# STM32F103C8BRD.net
KiCad netlist of a schematic drawn in EAGLE
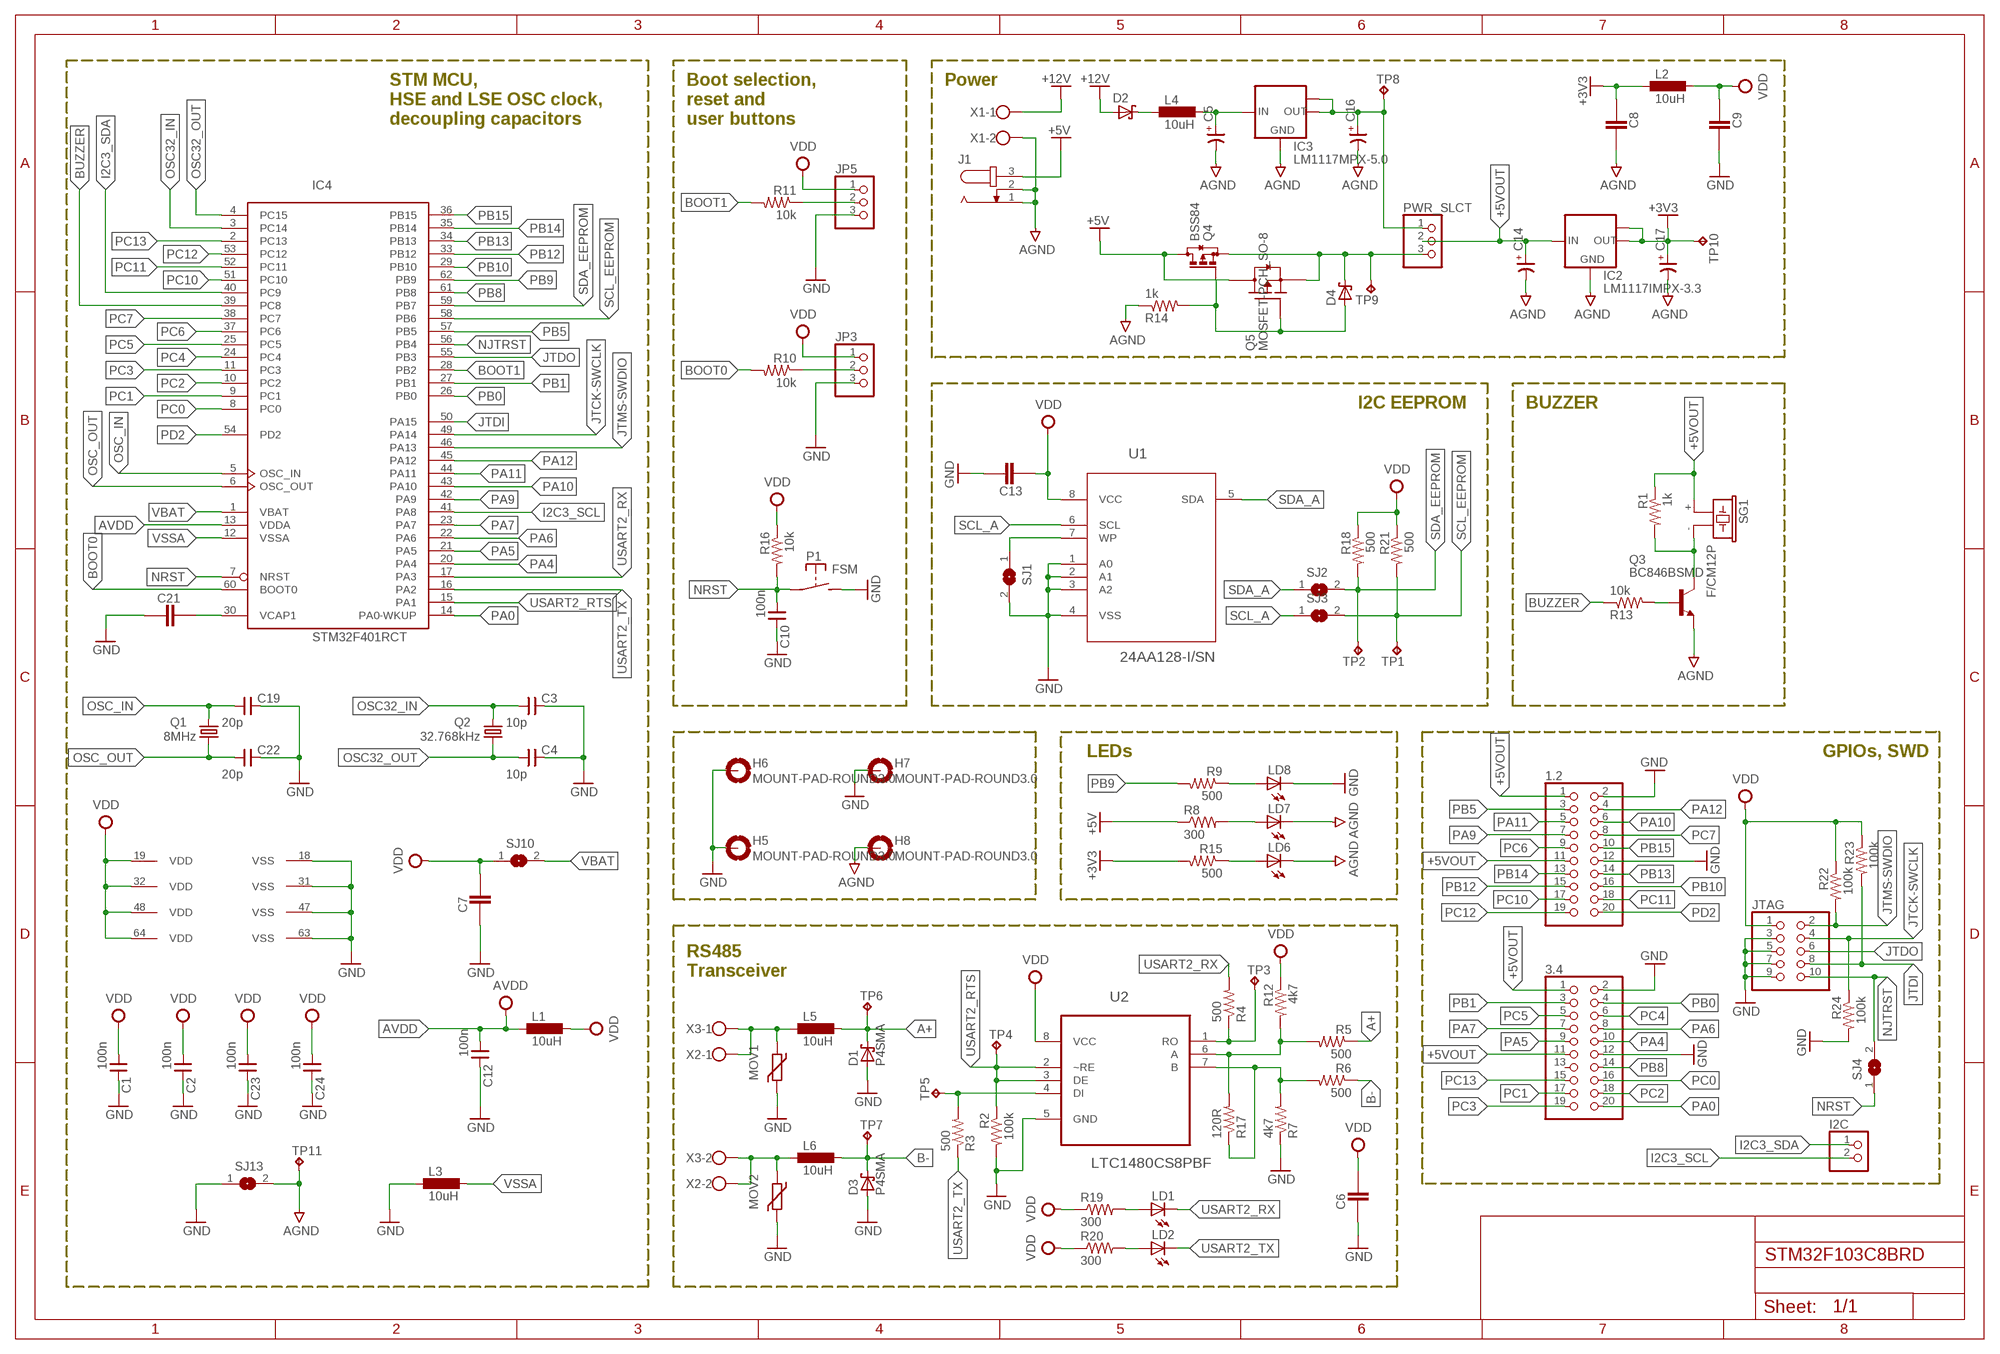
[diagram p0: schematic, sheet 1]

(export (version "E")
  (design (tool "Eeschema 10.0.6"))
  (components
    (comp (ref "1.2")
      (value "PINHD-2X10")
      (footprint "eagle-import:2X10")
      (libsource (lib "eagle-import") (part "PINHD-2X10"))
    )
    (comp (ref "3.4")
      (value "PINHD-2X10")
      (footprint "eagle-import:2X10")
      (libsource (lib "eagle-import") (part "PINHD-2X10"))
    )
    (comp (ref "C1")
      (value "100n")
      (footprint "eagle-import:0805")
      (libsource (lib "eagle-import") (part "CNP-0805"))
    )
    (comp (ref "C2")
      (value "100n")
      (footprint "eagle-import:0805")
      (libsource (lib "eagle-import") (part "CNP-0805"))
    )
    (comp (ref "C3")
      (value "10p")
      (footprint "eagle-import:0805")
      (libsource (lib "eagle-import") (part "CNP-0805"))
    )
    (comp (ref "C4")
      (value "10p")
      (footprint "eagle-import:0805")
      (libsource (lib "eagle-import") (part "CNP-0805"))
    )
    (comp (ref "C5")
      (value "CP-3258-TE-B")
      (footprint "eagle-import:3528-TE-B")
      (libsource (lib "eagle-import") (part "CP-3258-TE-B"))
    )
    (comp (ref "C6")
      (value "CAPACITOR_1206")
      (footprint "eagle-import:CAPC3215X168N")
      (libsource (lib "eagle-import") (part "CAPACITOR_1206"))
    )
    (comp (ref "C7")
      (value "CAPACITOR_1206")
      (footprint "eagle-import:CAPC3215X168N")
      (libsource (lib "eagle-import") (part "CAPACITOR_1206"))
    )
    (comp (ref "C8")
      (value "CAPACITOR_1206")
      (footprint "eagle-import:CAPC3215X168N")
      (libsource (lib "eagle-import") (part "CAPACITOR_1206"))
    )
    (comp (ref "C9")
      (value "CAPACITOR_1206")
      (footprint "eagle-import:CAPC3215X168N")
      (libsource (lib "eagle-import") (part "CAPACITOR_1206"))
    )
    (comp (ref "C10")
      (value "100n")
      (footprint "eagle-import:0805")
      (libsource (lib "eagle-import") (part "CNP-0805"))
    )
    (comp (ref "C12")
      (value "100n")
      (footprint "eagle-import:0805")
      (libsource (lib "eagle-import") (part "CNP-0805"))
    )
    (comp (ref "C13")
      (value "CAPACITOR_1206")
      (footprint "eagle-import:CAPC3215X168N")
      (libsource (lib "eagle-import") (part "CAPACITOR_1206"))
    )
    (comp (ref "C14")
      (value "CP-3258-TE-B")
      (footprint "eagle-import:3528-TE-B")
      (libsource (lib "eagle-import") (part "CP-3258-TE-B"))
    )
    (comp (ref "C16")
      (value "CP-3216-TE-A")
      (footprint "eagle-import:3216-TE-A")
      (libsource (lib "eagle-import") (part "CP-3216-TE-A"))
    )
    (comp (ref "C17")
      (value "CP-3216-TE-A")
      (footprint "eagle-import:3216-TE-A")
      (libsource (lib "eagle-import") (part "CP-3216-TE-A"))
    )
    (comp (ref "C19")
      (value "20p")
      (footprint "eagle-import:0805")
      (libsource (lib "eagle-import") (part "CNP-0805"))
    )
    (comp (ref "C21")
      (value "CAPACITOR_1206")
      (footprint "eagle-import:CAPC3215X168N")
      (libsource (lib "eagle-import") (part "CAPACITOR_1206"))
    )
    (comp (ref "C22")
      (value "20p")
      (footprint "eagle-import:0805")
      (libsource (lib "eagle-import") (part "CNP-0805"))
    )
    (comp (ref "C23")
      (value "100n")
      (footprint "eagle-import:0805")
      (libsource (lib "eagle-import") (part "CNP-0805"))
    )
    (comp (ref "C24")
      (value "100n")
      (footprint "eagle-import:0805")
      (libsource (lib "eagle-import") (part "CNP-0805"))
    )
    (comp (ref "D1")
      (value "P4SMA")
      (footprint "eagle-import:SMB")
      (libsource (lib "eagle-import") (part "SCHOTTKY-DIODESMD"))
    )
    (comp (ref "D2")
      (value "SCHOTTKY_SMA")
      (footprint "eagle-import:DIOM5326X292N")
      (libsource (lib "eagle-import") (part "SCHOTTKY_SMA"))
    )
    (comp (ref "D3")
      (value "P4SMA")
      (footprint "eagle-import:SMB")
      (libsource (lib "eagle-import") (part "SCHOTTKY-DIODESMD"))
    )
    (comp (ref "D4")
      (value "SCHOTTKY_SMA")
      (footprint "eagle-import:DIOM5326X292N")
      (libsource (lib "eagle-import") (part "SCHOTTKY_SMA"))
    )
    (comp (ref "H5")
      (value "MOUNT-PAD-ROUND3.0")
      (footprint "eagle-import:3,0-PAD")
      (libsource (lib "eagle-import") (part "MOUNT-PAD-ROUND3.0"))
    )
    (comp (ref "H6")
      (value "MOUNT-PAD-ROUND3.0")
      (footprint "eagle-import:3,0-PAD")
      (libsource (lib "eagle-import") (part "MOUNT-PAD-ROUND3.0"))
    )
    (comp (ref "H7")
      (value "MOUNT-PAD-ROUND3.0")
      (footprint "eagle-import:3,0-PAD")
      (libsource (lib "eagle-import") (part "MOUNT-PAD-ROUND3.0"))
    )
    (comp (ref "H8")
      (value "MOUNT-PAD-ROUND3.0")
      (footprint "eagle-import:3,0-PAD")
      (libsource (lib "eagle-import") (part "MOUNT-PAD-ROUND3.0"))
    )
    (comp (ref "I2C")
      (value "PINHD-1X2")
      (footprint "eagle-import:1X02")
      (libsource (lib "eagle-import") (part "PINHD-1X2"))
    )
    (comp (ref "IC2")
      (value "LM1117IMPX-3.3")
      (footprint "eagle-import:SOT223")
      (libsource (lib "eagle-import") (part "LM1117IMPX-3.3"))
    )
    (comp (ref "IC3")
      (value "LM1117MPX-5.0")
      (footprint "eagle-import:SOT223")
      (libsource (lib "eagle-import") (part "LM1117MPX-5.0"))
    )
    (comp (ref "IC4")
      (value "STM32F401RCT")
      (footprint "eagle-import:LQFP64")
      (libsource (lib "eagle-import") (part "STM32F401RTC"))
    )
    (comp (ref "J1")
      (value "JACK-PLUG1")
      (footprint "eagle-import:SPC4078")
      (libsource (lib "eagle-import") (part "JACK-PLUG1"))
    )
    (comp (ref "JP3")
      (value "PINHD-1X3")
      (footprint "eagle-import:1X03")
      (libsource (lib "eagle-import") (part "PINHD-1X3"))
    )
    (comp (ref "JP5")
      (value "PINHD-1X3")
      (footprint "eagle-import:1X03")
      (libsource (lib "eagle-import") (part "PINHD-1X3"))
    )
    (comp (ref "JTAG")
      (value "PINHD-2X5")
      (footprint "eagle-import:2X05")
      (libsource (lib "eagle-import") (part "PINHD-2X5"))
    )
    (comp (ref "L1")
      (value "10uH")
      (footprint "eagle-import:INDC1608X95N")
      (libsource (lib "eagle-import") (part "INDUCTOR_0603"))
    )
    (comp (ref "L2")
      (value "10uH")
      (footprint "eagle-import:INDC1608X95N")
      (libsource (lib "eagle-import") (part "INDUCTOR_0603"))
    )
    (comp (ref "L3")
      (value "10uH")
      (footprint "eagle-import:INDC1608X95N")
      (libsource (lib "eagle-import") (part "INDUCTOR_0603"))
    )
    (comp (ref "L4")
      (value "10uH")
      (footprint "eagle-import:INDC1608X95N")
      (libsource (lib "eagle-import") (part "INDUCTOR_0603"))
    )
    (comp (ref "L5")
      (value "10uH")
      (footprint "eagle-import:INDC1608X95N")
      (libsource (lib "eagle-import") (part "INDUCTOR_0603"))
    )
    (comp (ref "L6")
      (value "10uH")
      (footprint "eagle-import:INDC1608X95N")
      (libsource (lib "eagle-import") (part "INDUCTOR_0603"))
    )
    (comp (ref "LD1")
      (value "LEDCHIPLED_0805")
      (footprint "eagle-import:CHIPLED_0805")
      (libsource (lib "eagle-import") (part "LEDCHIPLED_0805"))
    )
    (comp (ref "LD2")
      (value "LEDCHIPLED_0805")
      (footprint "eagle-import:CHIPLED_0805")
      (libsource (lib "eagle-import") (part "LEDCHIPLED_0805"))
    )
    (comp (ref "LD6")
      (value "LEDCHIPLED_0805")
      (footprint "eagle-import:CHIPLED_0805")
      (libsource (lib "eagle-import") (part "LEDCHIPLED_0805"))
    )
    (comp (ref "LD7")
      (value "LEDCHIPLED_0805")
      (footprint "eagle-import:CHIPLED_0805")
      (libsource (lib "eagle-import") (part "LEDCHIPLED_0805"))
    )
    (comp (ref "LD8")
      (value "LEDCHIPLED_0805")
      (footprint "eagle-import:CHIPLED_0805")
      (libsource (lib "eagle-import") (part "LEDCHIPLED_0805"))
    )
    (comp (ref "MOV1")
      (value "VARISTOR_0805")
      (footprint "eagle-import:VARC2012X70N")
      (libsource (lib "eagle-import") (part "VARISTOR_0805"))
    )
    (comp (ref "MOV2")
      (value "VARISTOR_0805")
      (footprint "eagle-import:VARC2012X70N")
      (libsource (lib "eagle-import") (part "VARISTOR_0805"))
    )
    (comp (ref "P1")
      (value "FSM")
      (footprint "eagle-import:FSM")
      (libsource (lib "eagle-import") (part "FSM"))
    )
    (comp (ref "PWR_SLCT")
      (value "PINHD-1X3")
      (footprint "eagle-import:1X03")
      (libsource (lib "eagle-import") (part "PINHD-1X3"))
    )
    (comp (ref "Q1")
      (value "8MHz")
      (footprint "eagle-import:HC49_S")
      (libsource (lib "eagle-import") (part "CRYTALHC49S"))
    )
    (comp (ref "Q2")
      (value "32.768kHz")
      (footprint "eagle-import:TC26H")
      (libsource (lib "eagle-import") (part "CRYTALTC26H"))
    )
    (comp (ref "Q3")
      (value "BC846BSMD")
      (footprint "eagle-import:SOT23")
      (libsource (lib "eagle-import") (part "BC846SMDB"))
    )
    (comp (ref "Q4")
      (value "BSS84")
      (footprint "eagle-import:SOT23")
      (libsource (lib "eagle-import") (part "BSS84"))
    )
    (comp (ref "Q5")
      (value "MOSFET-PCH_SO-8")
      (footprint "eagle-import:SOIC127P600X175-8AN")
      (libsource (lib "eagle-import") (part "MOSFET-PCH_SO-8"))
    )
    (comp (ref "R1")
      (value "1k")
      (footprint "eagle-import:M0805")
      (libsource (lib "eagle-import") (part "R-US_M0805"))
    )
    (comp (ref "R2")
      (value "100k")
      (footprint "eagle-import:M0805")
      (libsource (lib "eagle-import") (part "R-US_M0805"))
    )
    (comp (ref "R3")
      (value "500")
      (footprint "eagle-import:M0805")
      (libsource (lib "eagle-import") (part "R-US_M0805"))
    )
    (comp (ref "R4")
      (value "500")
      (footprint "eagle-import:M0805")
      (libsource (lib "eagle-import") (part "R-US_M0805"))
    )
    (comp (ref "R5")
      (value "500")
      (footprint "eagle-import:M0805")
      (libsource (lib "eagle-import") (part "R-US_M0805"))
    )
    (comp (ref "R6")
      (value "500")
      (footprint "eagle-import:M0805")
      (libsource (lib "eagle-import") (part "R-US_M0805"))
    )
    (comp (ref "R7")
      (value "4k7")
      (footprint "eagle-import:M0805")
      (libsource (lib "eagle-import") (part "R-US_M0805"))
    )
    (comp (ref "R8")
      (value "300")
      (footprint "eagle-import:M0805")
      (libsource (lib "eagle-import") (part "R-US_M0805"))
    )
    (comp (ref "R9")
      (value "500")
      (footprint "eagle-import:M0805")
      (libsource (lib "eagle-import") (part "R-US_M0805"))
    )
    (comp (ref "R10")
      (value "10k")
      (footprint "eagle-import:M0805")
      (libsource (lib "eagle-import") (part "R-US_M0805"))
    )
    (comp (ref "R11")
      (value "10k")
      (footprint "eagle-import:M0805")
      (libsource (lib "eagle-import") (part "R-US_M0805"))
    )
    (comp (ref "R12")
      (value "4k7")
      (footprint "eagle-import:M0805")
      (libsource (lib "eagle-import") (part "R-US_M0805"))
    )
    (comp (ref "R13")
      (value "10k")
      (footprint "eagle-import:M0805")
      (libsource (lib "eagle-import") (part "R-US_M0805"))
    )
    (comp (ref "R14")
      (value "1k")
      (footprint "eagle-import:M0805")
      (libsource (lib "eagle-import") (part "R-US_M0805"))
    )
    (comp (ref "R15")
      (value "500")
      (footprint "eagle-import:M0805")
      (libsource (lib "eagle-import") (part "R-US_M0805"))
    )
    (comp (ref "R16")
      (value "10k")
      (footprint "eagle-import:M0805")
      (libsource (lib "eagle-import") (part "R-US_M0805"))
    )
    (comp (ref "R17")
      (value "120R")
      (footprint "eagle-import:M0805")
      (libsource (lib "eagle-import") (part "R-US_M0805"))
    )
    (comp (ref "R18")
      (value "500")
      (footprint "eagle-import:M0805")
      (libsource (lib "eagle-import") (part "R-US_M0805"))
    )
    (comp (ref "R19")
      (value "300")
      (footprint "eagle-import:M0805")
      (libsource (lib "eagle-import") (part "R-US_M0805"))
    )
    (comp (ref "R20")
      (value "300")
      (footprint "eagle-import:M0805")
      (libsource (lib "eagle-import") (part "R-US_M0805"))
    )
    (comp (ref "R21")
      (value "500")
      (footprint "eagle-import:M0805")
      (libsource (lib "eagle-import") (part "R-US_M0805"))
    )
    (comp (ref "R22")
      (value "100k")
      (footprint "eagle-import:M0805")
      (libsource (lib "eagle-import") (part "R-US_M0805"))
    )
    (comp (ref "R23")
      (value "100k")
      (footprint "eagle-import:M0805")
      (libsource (lib "eagle-import") (part "R-US_M0805"))
    )
    (comp (ref "R24")
      (value "100k")
      (footprint "eagle-import:M0805")
      (libsource (lib "eagle-import") (part "R-US_M0805"))
    )
    (comp (ref "SG1")
      (value "F/CM12P")
      (footprint "eagle-import:F_CM12P")
      (libsource (lib "eagle-import") (part "F/CM12P"))
    )
    (comp (ref "SJ1") (value "SJ") (footprint "eagle-import:SJ") (libsource (lib "eagle-import") (part "SJ")))
    (comp (ref "SJ2") (value "SJ") (footprint "eagle-import:SJ") (libsource (lib "eagle-import") (part "SJ")))
    (comp (ref "SJ3") (value "SJ") (footprint "eagle-import:SJ") (libsource (lib "eagle-import") (part "SJ")))
    (comp (ref "SJ4") (value "SJ") (footprint "eagle-import:SJ") (libsource (lib "eagle-import") (part "SJ")))
    (comp (ref "SJ10")
      (value "SJ")
      (footprint "eagle-import:SJ")
      (libsource (lib "eagle-import") (part "SJ"))
    )
    (comp (ref "SJ13")
      (value "SJ")
      (footprint "eagle-import:SJ")
      (libsource (lib "eagle-import") (part "SJ"))
    )
    (comp (ref "TP1")
      (value "TPTP10R")
      (footprint "eagle-import:TP10R")
      (libsource (lib "eagle-import") (part "TPTP10R"))
    )
    (comp (ref "TP2")
      (value "TPTP10R")
      (footprint "eagle-import:TP10R")
      (libsource (lib "eagle-import") (part "TPTP10R"))
    )
    (comp (ref "TP3")
      (value "TPTP10R")
      (footprint "eagle-import:TP10R")
      (libsource (lib "eagle-import") (part "TPTP10R"))
    )
    (comp (ref "TP4")
      (value "TPTP10R")
      (footprint "eagle-import:TP10R")
      (libsource (lib "eagle-import") (part "TPTP10R"))
    )
    (comp (ref "TP5")
      (value "TPTP10R")
      (footprint "eagle-import:TP10R")
      (libsource (lib "eagle-import") (part "TPTP10R"))
    )
    (comp (ref "TP6")
      (value "TPTP10R")
      (footprint "eagle-import:TP10R")
      (libsource (lib "eagle-import") (part "TPTP10R"))
    )
    (comp (ref "TP7")
      (value "TPTP10R")
      (footprint "eagle-import:TP10R")
      (libsource (lib "eagle-import") (part "TPTP10R"))
    )
    (comp (ref "TP8")
      (value "TPTP10R")
      (footprint "eagle-import:TP10R")
      (libsource (lib "eagle-import") (part "TPTP10R"))
    )
    (comp (ref "TP9")
      (value "TPTP10R")
      (footprint "eagle-import:TP10R")
      (libsource (lib "eagle-import") (part "TPTP10R"))
    )
    (comp (ref "TP10")
      (value "TPTP10R")
      (footprint "eagle-import:TP10R")
      (libsource (lib "eagle-import") (part "TPTP10R"))
    )
    (comp (ref "TP11")
      (value "TPTP10R")
      (footprint "eagle-import:TP10R")
      (libsource (lib "eagle-import") (part "TPTP10R"))
    )
    (comp (ref "U1")
      (value "24AA128-I/SN")
      (footprint "eagle-import:SOIC127P600X175-8N")
      (libsource (lib "eagle-import") (part "24AA128-I/SN"))
    )
    (comp (ref "U2")
      (value "LTC1480CS8PBF")
      (footprint "eagle-import:SOIC127P600X175-8N")
      (fields (field (name "MPN") "LTC1480CS8#PBF"))
      (libsource (lib "eagle-import") (part "LTC1480CS8PBF"))
    )
    (comp (ref "X1")
      (value "W237-102")
      (footprint "eagle-import:W237-102")
      (libsource (lib "eagle-import") (part "W237-102"))
    )
    (comp (ref "X2")
      (value "W237-102")
      (footprint "eagle-import:W237-102")
      (libsource (lib "eagle-import") (part "W237-102"))
    )
    (comp (ref "X3")
      (value "W237-102")
      (footprint "eagle-import:W237-102")
      (libsource (lib "eagle-import") (part "W237-102"))
    )
  )
  (nets
    (net (code "1") (name "+3V3") (class "Default")
      (node (ref "C17") (pin "+") (pinfunction "+_+") (pintype "passive"))
      (node (ref "C8") (pin "1") (pinfunction "1_1") (pintype "passive"))
      (node (ref "IC2") (pin "2") (pinfunction "OUT_2") (pintype "passive"))
      (node (ref "IC2") (pin "TAB") (pinfunction "OUT1_TAB") (pintype "passive"))
      (node (ref "L2") (pin "1") (pinfunction "1_1") (pintype "passive"))
      (node (ref "R15") (pin "2") (pinfunction "2_2") (pintype "passive"))
      (node (ref "TP10") (pin "TP") (pinfunction "TP_TP") (pintype "input"))
    )
    (net (code "2") (name "+5V") (class "Default")
      (node (ref "J1") (pin "3") (pinfunction "3_3") (pintype "passive"))
      (node (ref "Q4") (pin "3") (pinfunction "D_3") (pintype "passive"))
      (node (ref "Q5") (pin "5") (pinfunction "D_5") (pintype "passive"))
      (node (ref "R8") (pin "1") (pinfunction "1_1") (pintype "passive"))
    )
    (net (code "3") (name "+5VOUT") (class "Default")
      (node (ref "1.2") (pin "1") (pinfunction "1_1") (pintype "passive"))
      (node (ref "1.2") (pin "11") (pinfunction "11_11") (pintype "passive"))
      (node (ref "3.4") (pin "1") (pinfunction "1_1") (pintype "passive"))
      (node (ref "3.4") (pin "11") (pinfunction "11_11") (pintype "passive"))
      (node (ref "C14") (pin "+") (pinfunction "+_+") (pintype "passive"))
      (node (ref "IC2") (pin "3") (pinfunction "IN_3") (pintype "input"))
      (node (ref "PWR_SLCT") (pin "2") (pinfunction "2_2") (pintype "passive"))
      (node (ref "R1") (pin "1") (pinfunction "1_1") (pintype "passive"))
      (node (ref "SG1") (pin "+") (pinfunction "1_+") (pintype "passive"))
    )
    (net (code "4") (name "+12V") (class "Default")
      (node (ref "D2") (pin "A") (pinfunction "A_A") (pintype "passive"))
      (node (ref "X1") (pin "1") (pinfunction "KL_1") (pintype "passive"))
    )
    (net (code "5") (name "A+") (class "Default")
      (node (ref "D1") (pin "C") (pinfunction "C_C") (pintype "passive"))
      (node (ref "L5") (pin "2") (pinfunction "2_2") (pintype "passive"))
      (node (ref "R5") (pin "1") (pinfunction "1_1") (pintype "passive"))
      (node (ref "TP6") (pin "TP") (pinfunction "TP_TP") (pintype "input"))
    )
    (net (code "6") (name "AGND") (class "Default")
      (node (ref "C14") (pin "-") (pinfunction "-_-") (pintype "passive"))
      (node (ref "C16") (pin "-") (pinfunction "-_-") (pintype "passive"))
      (node (ref "C17") (pin "-") (pinfunction "-_-") (pintype "passive"))
      (node (ref "C5") (pin "-") (pinfunction "-_-") (pintype "passive"))
      (node (ref "C8") (pin "2") (pinfunction "2_2") (pintype "passive"))
      (node (ref "H8") (pin "B3,0") (pinfunction "MOUNT_B3,0") (pintype "passive"))
      (node (ref "IC2") (pin "1") (pinfunction "GND_1") (pintype "input"))
      (node (ref "IC3") (pin "1") (pinfunction "GND_1") (pintype "input"))
      (node (ref "J1") (pin "1") (pinfunction "1_1") (pintype "passive"))
      (node (ref "J1") (pin "2") (pinfunction "2_2") (pintype "passive"))
      (node (ref "LD6") (pin "C") (pinfunction "C_C") (pintype "passive"))
      (node (ref "LD7") (pin "C") (pinfunction "C_C") (pintype "passive"))
      (node (ref "Q3") (pin "2") (pinfunction "E_2") (pintype "passive"))
      (node (ref "R14") (pin "1") (pinfunction "1_1") (pintype "passive"))
      (node (ref "SJ13") (pin "2") (pinfunction "2_2") (pintype "passive"))
      (node (ref "TP11") (pin "TP") (pinfunction "TP_TP") (pintype "input"))
      (node (ref "X1") (pin "2") (pinfunction "KL_2") (pintype "passive"))
    )
    (net (code "7") (name "AVDD") (class "Default")
      (node (ref "C12") (pin "1") (pinfunction "1_1") (pintype "passive"))
      (node (ref "IC4") (pin "13") (pinfunction "VDDA_13") (pintype "power_in"))
      (node (ref "L1") (pin "1") (pinfunction "1_1") (pintype "passive"))
    )
    (net (code "8") (name "B-") (class "Default")
      (node (ref "D3") (pin "C") (pinfunction "C_C") (pintype "passive"))
      (node (ref "L6") (pin "2") (pinfunction "2_2") (pintype "passive"))
      (node (ref "R6") (pin "1") (pinfunction "1_1") (pintype "passive"))
      (node (ref "TP7") (pin "TP") (pinfunction "TP_TP") (pintype "input"))
    )
    (net (code "9") (name "BOOT0") (class "Default")
      (node (ref "IC4") (pin "60") (pinfunction "BOOT0_60") (pintype "input"))
      (node (ref "R10") (pin "2") (pinfunction "2_2") (pintype "passive"))
    )
    (net (code "10") (name "BOOT1") (class "Default")
      (node (ref "IC4") (pin "28") (pinfunction "PB2_28") (pintype "bidirectional"))
      (node (ref "R11") (pin "2") (pinfunction "2_2") (pintype "passive"))
    )
    (net (code "11") (name "BUZZER") (class "Default")
      (node (ref "IC4") (pin "39") (pinfunction "PC8_39") (pintype "bidirectional"))
      (node (ref "R13") (pin "1") (pinfunction "1_1") (pintype "passive"))
    )
    (net (code "12") (name "GND") (class "Default")
      (node (ref "1.2") (pin "12") (pinfunction "12_12") (pintype "passive"))
      (node (ref "1.2") (pin "2") (pinfunction "2_2") (pintype "passive"))
      (node (ref "3.4") (pin "12") (pinfunction "12_12") (pintype "passive"))
      (node (ref "3.4") (pin "2") (pinfunction "2_2") (pintype "passive"))
      (node (ref "C1") (pin "2") (pinfunction "2_2") (pintype "passive"))
      (node (ref "C10") (pin "2") (pinfunction "2_2") (pintype "passive"))
      (node (ref "C12") (pin "2") (pinfunction "2_2") (pintype "passive"))
      (node (ref "C13") (pin "2") (pinfunction "2_2") (pintype "passive"))
      (node (ref "C19") (pin "2") (pinfunction "2_2") (pintype "passive"))
      (node (ref "C2") (pin "2") (pinfunction "2_2") (pintype "passive"))
      (node (ref "C21") (pin "1") (pinfunction "1_1") (pintype "passive"))
      (node (ref "C22") (pin "2") (pinfunction "2_2") (pintype "passive"))
      (node (ref "C23") (pin "2") (pinfunction "2_2") (pintype "passive"))
      (node (ref "C24") (pin "2") (pinfunction "2_2") (pintype "passive"))
      (node (ref "C3") (pin "2") (pinfunction "2_2") (pintype "passive"))
      (node (ref "C4") (pin "2") (pinfunction "2_2") (pintype "passive"))
      (node (ref "C6") (pin "1") (pinfunction "1_1") (pintype "passive"))
      (node (ref "C7") (pin "1") (pinfunction "1_1") (pintype "passive"))
      (node (ref "C9") (pin "2") (pinfunction "2_2") (pintype "passive"))
      (node (ref "D1") (pin "A") (pinfunction "A_A") (pintype "passive"))
      (node (ref "D3") (pin "A") (pinfunction "A_A") (pintype "passive"))
      (node (ref "H5") (pin "B3,0") (pinfunction "MOUNT_B3,0") (pintype "passive"))
      (node (ref "H6") (pin "B3,0") (pinfunction "MOUNT_B3,0") (pintype "passive"))
      (node (ref "H7") (pin "B3,0") (pinfunction "MOUNT_B3,0") (pintype "passive"))
      (node (ref "IC4") (pin "18") (pinfunction "VSS_18") (pintype "power_in"))
      (node (ref "IC4") (pin "31") (pinfunction "VSS_31") (pintype "power_in"))
      (node (ref "IC4") (pin "47") (pinfunction "VSS_47") (pintype "power_in"))
      (node (ref "IC4") (pin "63") (pinfunction "VSS_63") (pintype "power_in"))
      (node (ref "JP3") (pin "3") (pinfunction "3_3") (pintype "passive"))
      (node (ref "JP5") (pin "3") (pinfunction "3_3") (pintype "passive"))
      (node (ref "JTAG") (pin "3") (pinfunction "3_3") (pintype "passive"))
      (node (ref "JTAG") (pin "5") (pinfunction "5_5") (pintype "passive"))
      (node (ref "JTAG") (pin "7") (pinfunction "7_7") (pintype "passive"))
      (node (ref "JTAG") (pin "9") (pinfunction "9_9") (pintype "passive"))
      (node (ref "L3") (pin "1") (pinfunction "1_1") (pintype "passive"))
      (node (ref "LD8") (pin "C") (pinfunction "C_C") (pintype "passive"))
      (node (ref "MOV1") (pin "1") (pinfunction "1_1") (pintype "passive"))
      (node (ref "MOV2") (pin "1") (pinfunction "1_1") (pintype "passive"))
      (node (ref "P1") (pin "P$2") (pinfunction "S_P$2") (pintype "passive"))
      (node (ref "R2") (pin "2") (pinfunction "2_2") (pintype "passive"))
      (node (ref "R24") (pin "2") (pinfunction "2_2") (pintype "passive"))
      (node (ref "R7") (pin "1") (pinfunction "1_1") (pintype "passive"))
      (node (ref "SJ1") (pin "2") (pinfunction "2_2") (pintype "passive"))
      (node (ref "SJ13") (pin "1") (pinfunction "1_1") (pintype "passive"))
      (node (ref "U1") (pin "1") (pinfunction "A0_1") (pintype "input"))
      (node (ref "U1") (pin "2") (pinfunction "A1_2") (pintype "input"))
      (node (ref "U1") (pin "3") (pinfunction "A2_3") (pintype "input"))
      (node (ref "U1") (pin "4") (pinfunction "VSS_4") (pintype "power_in"))
      (node (ref "U2") (pin "5") (pinfunction "GND_5") (pintype "passive"))
    )
    (net (code "13") (name "I2C3_SCL") (class "Default")
      (node (ref "I2C") (pin "2") (pinfunction "2_2") (pintype "passive"))
      (node (ref "IC4") (pin "41") (pinfunction "PA8_41") (pintype "bidirectional"))
    )
    (net (code "14") (name "I2C3_SDA") (class "Default")
      (node (ref "I2C") (pin "1") (pinfunction "1_1") (pintype "passive"))
      (node (ref "IC4") (pin "40") (pinfunction "PC9_40") (pintype "bidirectional"))
    )
    (net (code "15") (name "JTCK-SWCLK") (class "Default")
      (node (ref "IC4") (pin "49") (pinfunction "PA14_49") (pintype "bidirectional"))
      (node (ref "JTAG") (pin "4") (pinfunction "4_4") (pintype "passive"))
      (node (ref "R24") (pin "1") (pinfunction "1_1") (pintype "passive"))
    )
    (net (code "16") (name "JTDI") (class "Default")
      (node (ref "IC4") (pin "50") (pinfunction "PA15_50") (pintype "bidirectional"))
      (node (ref "JTAG") (pin "8") (pinfunction "8_8") (pintype "passive"))
      (node (ref "R23") (pin "2") (pinfunction "2_2") (pintype "passive"))
    )
    (net (code "17") (name "JTDO") (class "Default")
      (node (ref "IC4") (pin "55") (pinfunction "PB3_55") (pintype "bidirectional"))
      (node (ref "JTAG") (pin "6") (pinfunction "6_6") (pintype "passive"))
    )
    (net (code "18") (name "JTMS-SWDIO") (class "Default")
      (node (ref "IC4") (pin "46") (pinfunction "PA13_46") (pintype "bidirectional"))
      (node (ref "JTAG") (pin "2") (pinfunction "2_2") (pintype "passive"))
      (node (ref "R22") (pin "2") (pinfunction "2_2") (pintype "passive"))
    )
    (net (code "19") (name "NJTRST") (class "Default")
      (node (ref "IC4") (pin "56") (pinfunction "PB4_56") (pintype "bidirectional"))
      (node (ref "JTAG") (pin "10") (pinfunction "10_10") (pintype "passive"))
      (node (ref "SJ4") (pin "2") (pinfunction "2_2") (pintype "passive"))
    )
    (net (code "20") (name "NRST") (class "Default")
      (node (ref "C10") (pin "1") (pinfunction "1_1") (pintype "passive"))
      (node (ref "IC4") (pin "7") (pinfunction "NRST_7") (pintype "bidirectional"))
      (node (ref "P1") (pin "P$1") (pinfunction "P_P$1") (pintype "passive"))
      (node (ref "R16") (pin "2") (pinfunction "2_2") (pintype "passive"))
      (node (ref "SJ4") (pin "1") (pinfunction "1_1") (pintype "passive"))
    )
    (net (code "21") (name "Net-(D2-PadK)") (class "Default")
      (node (ref "D2") (pin "K") (pinfunction "K_K") (pintype "passive"))
      (node (ref "L4") (pin "1") (pinfunction "1_1") (pintype "passive"))
    )
    (net (code "22") (name "Net-(IC3-IN)") (class "Default")
      (node (ref "C5") (pin "+") (pinfunction "+_+") (pintype "passive"))
      (node (ref "IC3") (pin "3") (pinfunction "IN_3") (pintype "input"))
      (node (ref "L4") (pin "2") (pinfunction "2_2") (pintype "passive"))
    )
    (net (code "23") (name "Net-(IC3-OUT)") (class "Default")
      (node (ref "C16") (pin "+") (pinfunction "+_+") (pintype "passive"))
      (node (ref "IC3") (pin "2") (pinfunction "OUT_2") (pintype "passive"))
      (node (ref "IC3") (pin "TAB") (pinfunction "OUT1_TAB") (pintype "passive"))
      (node (ref "PWR_SLCT") (pin "1") (pinfunction "1_1") (pintype "passive"))
      (node (ref "TP8") (pin "TP") (pinfunction "TP_TP") (pintype "input"))
    )
    (net (code "24") (name "Net-(IC4A-VCAP1)") (class "Default")
      (node (ref "C21") (pin "2") (pinfunction "2_2") (pintype "passive"))
      (node (ref "IC4") (pin "30") (pinfunction "VCAP1_30") (pintype "power_in"))
    )
    (net (code "25") (name "Net-(JP3-Pad2)") (class "Default")
      (node (ref "JP3") (pin "2") (pinfunction "2_2") (pintype "passive"))
      (node (ref "R10") (pin "1") (pinfunction "1_1") (pintype "passive"))
    )
    (net (code "26") (name "Net-(JP5-Pad2)") (class "Default")
      (node (ref "JP5") (pin "2") (pinfunction "2_2") (pintype "passive"))
      (node (ref "R11") (pin "1") (pinfunction "1_1") (pintype "passive"))
    )
    (net (code "27") (name "Net-(LD1-PadA)") (class "Default")
      (node (ref "LD1") (pin "A") (pinfunction "A_A") (pintype "passive"))
      (node (ref "R19") (pin "2") (pinfunction "2_2") (pintype "passive"))
    )
    (net (code "28") (name "Net-(LD2-PadA)") (class "Default")
      (node (ref "LD2") (pin "A") (pinfunction "A_A") (pintype "passive"))
      (node (ref "R20") (pin "2") (pinfunction "2_2") (pintype "passive"))
    )
    (net (code "29") (name "Net-(LD6-PadA)") (class "Default")
      (node (ref "LD6") (pin "A") (pinfunction "A_A") (pintype "passive"))
      (node (ref "R15") (pin "1") (pinfunction "1_1") (pintype "passive"))
    )
    (net (code "30") (name "Net-(LD7-PadA)") (class "Default")
      (node (ref "LD7") (pin "A") (pinfunction "A_A") (pintype "passive"))
      (node (ref "R8") (pin "2") (pinfunction "2_2") (pintype "passive"))
    )
    (net (code "31") (name "Net-(LD8-PadA)") (class "Default")
      (node (ref "LD8") (pin "A") (pinfunction "A_A") (pintype "passive"))
      (node (ref "R9") (pin "1") (pinfunction "1_1") (pintype "passive"))
    )
    (net (code "32") (name "Net-(Q3-B)") (class "Default")
      (node (ref "Q3") (pin "1") (pinfunction "B_1") (pintype "passive"))
      (node (ref "R13") (pin "2") (pinfunction "2_2") (pintype "passive"))
    )
    (net (code "33") (name "Net-(Q3-C)") (class "Default")
      (node (ref "Q3") (pin "3") (pinfunction "C_3") (pintype "passive"))
      (node (ref "R1") (pin "2") (pinfunction "2_2") (pintype "passive"))
      (node (ref "SG1") (pin "-") (pinfunction "2_-") (pintype "passive"))
    )
    (net (code "34") (name "Net-(Q4-G)") (class "Default")
      (node (ref "D4") (pin "A") (pinfunction "A_A") (pintype "passive"))
      (node (ref "Q4") (pin "1") (pinfunction "G_1") (pintype "passive"))
      (node (ref "Q5") (pin "4") (pinfunction "G_4") (pintype "passive"))
      (node (ref "R14") (pin "2") (pinfunction "2_2") (pintype "passive"))
    )
    (net (code "35") (name "Net-(Q4-S)") (class "Default")
      (node (ref "D4") (pin "K") (pinfunction "K_K") (pintype "passive"))
      (node (ref "PWR_SLCT") (pin "3") (pinfunction "3_3") (pintype "passive"))
      (node (ref "Q4") (pin "2") (pinfunction "S_2") (pintype "passive"))
      (node (ref "Q5") (pin "1") (pinfunction "S_1") (pintype "passive"))
      (node (ref "TP9") (pin "TP") (pinfunction "TP_TP") (pintype "input"))
    )
    (net (code "36") (name "Net-(U1-WP)") (class "Default")
      (node (ref "SJ1") (pin "1") (pinfunction "1_1") (pintype "passive"))
      (node (ref "U1") (pin "7") (pinfunction "WP_7") (pintype "input"))
    )
    (net (code "37") (name "Net-(U2-A)") (class "Default")
      (node (ref "R12") (pin "2") (pinfunction "2_2") (pintype "passive"))
      (node (ref "R17") (pin "2") (pinfunction "2_2") (pintype "passive"))
      (node (ref "R5") (pin "2") (pinfunction "2_2") (pintype "passive"))
      (node (ref "U2") (pin "6") (pinfunction "A_6") (pintype "bidirectional"))
    )
    (net (code "38") (name "Net-(U2-B)") (class "Default")
      (node (ref "R17") (pin "1") (pinfunction "1_1") (pintype "passive"))
      (node (ref "R6") (pin "2") (pinfunction "2_2") (pintype "passive"))
      (node (ref "R7") (pin "2") (pinfunction "2_2") (pintype "passive"))
      (node (ref "U2") (pin "7") (pinfunction "B_7") (pintype "bidirectional"))
    )
    (net (code "39") (name "Net-(U2-DI)") (class "Default")
      (node (ref "R3") (pin "2") (pinfunction "2_2") (pintype "passive"))
      (node (ref "TP5") (pin "TP") (pinfunction "TP_TP") (pintype "input"))
      (node (ref "U2") (pin "4") (pinfunction "DI_4") (pintype "input"))
    )
    (net (code "40") (name "Net-(U2-RO)") (class "Default")
      (node (ref "R4") (pin "1") (pinfunction "1_1") (pintype "passive"))
      (node (ref "TP3") (pin "TP") (pinfunction "TP_TP") (pintype "input"))
      (node (ref "U2") (pin "1") (pinfunction "RO_1") (pintype "output"))
    )
    (net (code "41") (name "Net-(X2A-KL)") (class "Default")
      (node (ref "L5") (pin "1") (pinfunction "1_1") (pintype "passive"))
      (node (ref "MOV1") (pin "2") (pinfunction "2_2") (pintype "passive"))
      (node (ref "X2") (pin "1") (pinfunction "KL_1") (pintype "passive"))
      (node (ref "X3") (pin "1") (pinfunction "KL_1") (pintype "passive"))
    )
    (net (code "42") (name "Net-(X2B-KL)") (class "Default")
      (node (ref "L6") (pin "1") (pinfunction "1_1") (pintype "passive"))
      (node (ref "MOV2") (pin "2") (pinfunction "2_2") (pintype "passive"))
      (node (ref "X2") (pin "2") (pinfunction "KL_2") (pintype "passive"))
      (node (ref "X3") (pin "2") (pinfunction "KL_2") (pintype "passive"))
    )
    (net (code "43") (name "OSC32_IN") (class "Default")
      (node (ref "C3") (pin "1") (pinfunction "1_1") (pintype "passive"))
      (node (ref "IC4") (pin "3") (pinfunction "PC14_3") (pintype "bidirectional"))
      (node (ref "Q2") (pin "2") (pinfunction "2_2") (pintype "passive"))
    )
    (net (code "44") (name "OSC32_OUT") (class "Default")
      (node (ref "C4") (pin "1") (pinfunction "1_1") (pintype "passive"))
      (node (ref "IC4") (pin "4") (pinfunction "PC15_4") (pintype "bidirectional"))
      (node (ref "Q2") (pin "1") (pinfunction "1_1") (pintype "passive"))
    )
    (net (code "45") (name "OSC_IN") (class "Default")
      (node (ref "C19") (pin "1") (pinfunction "1_1") (pintype "passive"))
      (node (ref "IC4") (pin "5") (pinfunction "OSC_IN_5") (pintype "bidirectional"))
      (node (ref "Q1") (pin "2") (pinfunction "2_2") (pintype "passive"))
    )
    (net (code "46") (name "OSC_OUT") (class "Default")
      (node (ref "C22") (pin "1") (pinfunction "1_1") (pintype "passive"))
      (node (ref "IC4") (pin "6") (pinfunction "OSC_OUT_6") (pintype "bidirectional"))
      (node (ref "Q1") (pin "1") (pinfunction "1_1") (pintype "passive"))
    )
    (net (code "47") (name "PA0") (class "Default")
      (node (ref "3.4") (pin "20") (pinfunction "20_20") (pintype "passive"))
      (node (ref "IC4") (pin "14") (pinfunction "PA0-WKUP_14") (pintype "bidirectional"))
    )
    (net (code "48") (name "PA4") (class "Default")
      (node (ref "3.4") (pin "10") (pinfunction "10_10") (pintype "passive"))
      (node (ref "IC4") (pin "20") (pinfunction "PA4_20") (pintype "bidirectional"))
    )
    (net (code "49") (name "PA5") (class "Default")
      (node (ref "3.4") (pin "9") (pinfunction "9_9") (pintype "passive"))
      (node (ref "IC4") (pin "21") (pinfunction "PA5_21") (pintype "bidirectional"))
    )
    (net (code "50") (name "PA6") (class "Default")
      (node (ref "3.4") (pin "8") (pinfunction "8_8") (pintype "passive"))
      (node (ref "IC4") (pin "22") (pinfunction "PA6_22") (pintype "bidirectional"))
    )
    (net (code "51") (name "PA7") (class "Default")
      (node (ref "3.4") (pin "7") (pinfunction "7_7") (pintype "passive"))
      (node (ref "IC4") (pin "23") (pinfunction "PA7_23") (pintype "bidirectional"))
    )
    (net (code "52") (name "PA9") (class "Default")
      (node (ref "1.2") (pin "7") (pinfunction "7_7") (pintype "passive"))
      (node (ref "IC4") (pin "42") (pinfunction "PA9_42") (pintype "bidirectional"))
    )
    (net (code "53") (name "PA10") (class "Default")
      (node (ref "1.2") (pin "6") (pinfunction "6_6") (pintype "passive"))
      (node (ref "IC4") (pin "43") (pinfunction "PA10_43") (pintype "bidirectional"))
    )
    (net (code "54") (name "PA11") (class "Default")
      (node (ref "1.2") (pin "5") (pinfunction "5_5") (pintype "passive"))
      (node (ref "IC4") (pin "44") (pinfunction "PA11_44") (pintype "bidirectional"))
    )
    (net (code "55") (name "PA12") (class "Default")
      (node (ref "1.2") (pin "4") (pinfunction "4_4") (pintype "passive"))
      (node (ref "IC4") (pin "45") (pinfunction "PA12_45") (pintype "bidirectional"))
    )
    (net (code "56") (name "PB0") (class "Default")
      (node (ref "3.4") (pin "4") (pinfunction "4_4") (pintype "passive"))
      (node (ref "IC4") (pin "26") (pinfunction "PB0_26") (pintype "bidirectional"))
    )
    (net (code "57") (name "PB1") (class "Default")
      (node (ref "3.4") (pin "3") (pinfunction "3_3") (pintype "passive"))
      (node (ref "IC4") (pin "27") (pinfunction "PB1_27") (pintype "bidirectional"))
    )
    (net (code "58") (name "PB5") (class "Default")
      (node (ref "1.2") (pin "3") (pinfunction "3_3") (pintype "passive"))
      (node (ref "IC4") (pin "57") (pinfunction "PB5_57") (pintype "bidirectional"))
    )
    (net (code "59") (name "PB8") (class "Default")
      (node (ref "3.4") (pin "14") (pinfunction "14_14") (pintype "passive"))
      (node (ref "IC4") (pin "61") (pinfunction "PB8_61") (pintype "bidirectional"))
    )
    (net (code "60") (name "PB9") (class "Default")
      (node (ref "IC4") (pin "62") (pinfunction "PB9_62") (pintype "bidirectional"))
      (node (ref "R9") (pin "2") (pinfunction "2_2") (pintype "passive"))
    )
    (net (code "61") (name "PB10") (class "Default")
      (node (ref "1.2") (pin "16") (pinfunction "16_16") (pintype "passive"))
      (node (ref "IC4") (pin "29") (pinfunction "PB10_29") (pintype "bidirectional"))
    )
    (net (code "62") (name "PB12") (class "Default")
      (node (ref "1.2") (pin "15") (pinfunction "15_15") (pintype "passive"))
      (node (ref "IC4") (pin "33") (pinfunction "PB12_33") (pintype "bidirectional"))
    )
    (net (code "63") (name "PB13") (class "Default")
      (node (ref "1.2") (pin "14") (pinfunction "14_14") (pintype "passive"))
      (node (ref "IC4") (pin "34") (pinfunction "PB13_34") (pintype "bidirectional"))
    )
    (net (code "64") (name "PB14") (class "Default")
      (node (ref "1.2") (pin "13") (pinfunction "13_13") (pintype "passive"))
      (node (ref "IC4") (pin "35") (pinfunction "PB14_35") (pintype "bidirectional"))
    )
    (net (code "65") (name "PB15") (class "Default")
      (node (ref "1.2") (pin "10") (pinfunction "10_10") (pintype "passive"))
      (node (ref "IC4") (pin "36") (pinfunction "PB15_36") (pintype "bidirectional"))
    )
    (net (code "66") (name "PC0") (class "Default")
      (node (ref "3.4") (pin "16") (pinfunction "16_16") (pintype "passive"))
      (node (ref "IC4") (pin "8") (pinfunction "PC0_8") (pintype "bidirectional"))
    )
    (net (code "67") (name "PC1") (class "Default")
      (node (ref "3.4") (pin "17") (pinfunction "17_17") (pintype "passive"))
      (node (ref "IC4") (pin "9") (pinfunction "PC1_9") (pintype "bidirectional"))
    )
    (net (code "68") (name "PC2") (class "Default")
      (node (ref "3.4") (pin "18") (pinfunction "18_18") (pintype "passive"))
      (node (ref "IC4") (pin "10") (pinfunction "PC2_10") (pintype "bidirectional"))
    )
    (net (code "69") (name "PC3") (class "Default")
      (node (ref "3.4") (pin "19") (pinfunction "19_19") (pintype "passive"))
      (node (ref "IC4") (pin "11") (pinfunction "PC3_11") (pintype "bidirectional"))
    )
    (net (code "70") (name "PC4") (class "Default")
      (node (ref "3.4") (pin "6") (pinfunction "6_6") (pintype "passive"))
      (node (ref "IC4") (pin "24") (pinfunction "PC4_24") (pintype "bidirectional"))
    )
    (net (code "71") (name "PC5") (class "Default")
      (node (ref "3.4") (pin "5") (pinfunction "5_5") (pintype "passive"))
      (node (ref "IC4") (pin "25") (pinfunction "PC5_25") (pintype "bidirectional"))
    )
    (net (code "72") (name "PC6") (class "Default")
      (node (ref "1.2") (pin "9") (pinfunction "9_9") (pintype "passive"))
      (node (ref "IC4") (pin "37") (pinfunction "PC6_37") (pintype "bidirectional"))
    )
    (net (code "73") (name "PC7") (class "Default")
      (node (ref "1.2") (pin "8") (pinfunction "8_8") (pintype "passive"))
      (node (ref "IC4") (pin "38") (pinfunction "PC7_38") (pintype "bidirectional"))
    )
    (net (code "74") (name "PC10") (class "Default")
      (node (ref "1.2") (pin "17") (pinfunction "17_17") (pintype "passive"))
      (node (ref "IC4") (pin "51") (pinfunction "PC10_51") (pintype "bidirectional"))
    )
    (net (code "75") (name "PC11") (class "Default")
      (node (ref "1.2") (pin "18") (pinfunction "18_18") (pintype "passive"))
      (node (ref "IC4") (pin "52") (pinfunction "PC11_52") (pintype "bidirectional"))
    )
    (net (code "76") (name "PC12") (class "Default")
      (node (ref "1.2") (pin "19") (pinfunction "19_19") (pintype "passive"))
      (node (ref "IC4") (pin "53") (pinfunction "PC12_53") (pintype "bidirectional"))
    )
    (net (code "77") (name "PC13") (class "Default")
      (node (ref "3.4") (pin "15") (pinfunction "15_15") (pintype "passive"))
      (node (ref "IC4") (pin "2") (pinfunction "PC13_2") (pintype "bidirectional"))
    )
    (net (code "78") (name "PD2") (class "Default")
      (node (ref "1.2") (pin "20") (pinfunction "20_20") (pintype "passive"))
      (node (ref "IC4") (pin "54") (pinfunction "PD2_54") (pintype "bidirectional"))
    )
    (net (code "79") (name "SCL_A") (class "Default")
      (node (ref "SJ3") (pin "1") (pinfunction "1_1") (pintype "passive"))
      (node (ref "U1") (pin "6") (pinfunction "SCL_6") (pintype "input"))
    )
    (net (code "80") (name "SCL_EEPROM") (class "Default")
      (node (ref "IC4") (pin "58") (pinfunction "PB6_58") (pintype "bidirectional"))
      (node (ref "R21") (pin "2") (pinfunction "2_2") (pintype "passive"))
      (node (ref "SJ3") (pin "2") (pinfunction "2_2") (pintype "passive"))
      (node (ref "TP1") (pin "TP") (pinfunction "TP_TP") (pintype "input"))
    )
    (net (code "81") (name "SDA_A") (class "Default")
      (node (ref "SJ2") (pin "1") (pinfunction "1_1") (pintype "passive"))
      (node (ref "U1") (pin "5") (pinfunction "SDA_5") (pintype "bidirectional"))
    )
    (net (code "82") (name "SDA_EEPROM") (class "Default")
      (node (ref "IC4") (pin "59") (pinfunction "PB7_59") (pintype "bidirectional"))
      (node (ref "R18") (pin "2") (pinfunction "2_2") (pintype "passive"))
      (node (ref "SJ2") (pin "2") (pinfunction "2_2") (pintype "passive"))
      (node (ref "TP2") (pin "TP") (pinfunction "TP_TP") (pintype "input"))
    )
    (net (code "83") (name "USART2_RTS") (class "Default")
      (node (ref "IC4") (pin "15") (pinfunction "PA1_15") (pintype "bidirectional"))
      (node (ref "R2") (pin "1") (pinfunction "1_1") (pintype "passive"))
      (node (ref "TP4") (pin "TP") (pinfunction "TP_TP") (pintype "input"))
      (node (ref "U2") (pin "2") (pinfunction "~{RE}_2") (pintype "input"))
      (node (ref "U2") (pin "3") (pinfunction "DE_3") (pintype "input"))
    )
    (net (code "84") (name "USART2_RX") (class "Default")
      (node (ref "IC4") (pin "17") (pinfunction "PA3_17") (pintype "bidirectional"))
      (node (ref "LD1") (pin "C") (pinfunction "C_C") (pintype "passive"))
      (node (ref "R4") (pin "2") (pinfunction "2_2") (pintype "passive"))
    )
    (net (code "85") (name "USART2_TX") (class "Default")
      (node (ref "IC4") (pin "16") (pinfunction "PA2_16") (pintype "bidirectional"))
      (node (ref "LD2") (pin "C") (pinfunction "C_C") (pintype "passive"))
      (node (ref "R3") (pin "1") (pinfunction "1_1") (pintype "passive"))
    )
    (net (code "86") (name "VBAT") (class "Default")
      (node (ref "IC4") (pin "1") (pinfunction "VBAT_1") (pintype "power_in"))
      (node (ref "SJ10") (pin "2") (pinfunction "2_2") (pintype "passive"))
    )
    (net (code "87") (name "VDD") (class "Default")
      (node (ref "C1") (pin "1") (pinfunction "1_1") (pintype "passive"))
      (node (ref "C13") (pin "1") (pinfunction "1_1") (pintype "passive"))
      (node (ref "C2") (pin "1") (pinfunction "1_1") (pintype "passive"))
      (node (ref "C23") (pin "1") (pinfunction "1_1") (pintype "passive"))
      (node (ref "C24") (pin "1") (pinfunction "1_1") (pintype "passive"))
      (node (ref "C6") (pin "2") (pinfunction "2_2") (pintype "passive"))
      (node (ref "C7") (pin "2") (pinfunction "2_2") (pintype "passive"))
      (node (ref "C9") (pin "1") (pinfunction "1_1") (pintype "passive"))
      (node (ref "IC4") (pin "19") (pinfunction "VDD_19") (pintype "power_in"))
      (node (ref "IC4") (pin "32") (pinfunction "VDD_32") (pintype "power_in"))
      (node (ref "IC4") (pin "48") (pinfunction "VDD_48") (pintype "power_in"))
      (node (ref "IC4") (pin "64") (pinfunction "VDD_64") (pintype "power_in"))
      (node (ref "JP3") (pin "1") (pinfunction "1_1") (pintype "passive"))
      (node (ref "JP5") (pin "1") (pinfunction "1_1") (pintype "passive"))
      (node (ref "JTAG") (pin "1") (pinfunction "1_1") (pintype "passive"))
      (node (ref "L1") (pin "2") (pinfunction "2_2") (pintype "passive"))
      (node (ref "L2") (pin "2") (pinfunction "2_2") (pintype "passive"))
      (node (ref "R12") (pin "1") (pinfunction "1_1") (pintype "passive"))
      (node (ref "R16") (pin "1") (pinfunction "1_1") (pintype "passive"))
      (node (ref "R18") (pin "1") (pinfunction "1_1") (pintype "passive"))
      (node (ref "R19") (pin "1") (pinfunction "1_1") (pintype "passive"))
      (node (ref "R20") (pin "1") (pinfunction "1_1") (pintype "passive"))
      (node (ref "R21") (pin "1") (pinfunction "1_1") (pintype "passive"))
      (node (ref "R22") (pin "1") (pinfunction "1_1") (pintype "passive"))
      (node (ref "R23") (pin "1") (pinfunction "1_1") (pintype "passive"))
      (node (ref "SJ10") (pin "1") (pinfunction "1_1") (pintype "passive"))
      (node (ref "U1") (pin "8") (pinfunction "VCC_8") (pintype "power_in"))
      (node (ref "U2") (pin "8") (pinfunction "VCC_8") (pintype "power_in"))
    )
    (net (code "88") (name "VSSA") (class "Default")
      (node (ref "IC4") (pin "12") (pinfunction "VSSA_12") (pintype "power_in"))
      (node (ref "L3") (pin "2") (pinfunction "2_2") (pintype "passive"))
    )
    (net (code "89") (name "unconnected-(3.4-Pad13)") (class "Default")
      (node (ref "3.4") (pin "13") (pinfunction "13_13") (pintype "passive"))
    )
  )
)
